# Adafruit_USB_Type_C_PD_Switchable.net
KiCad netlist of a schematic drawn in EAGLE
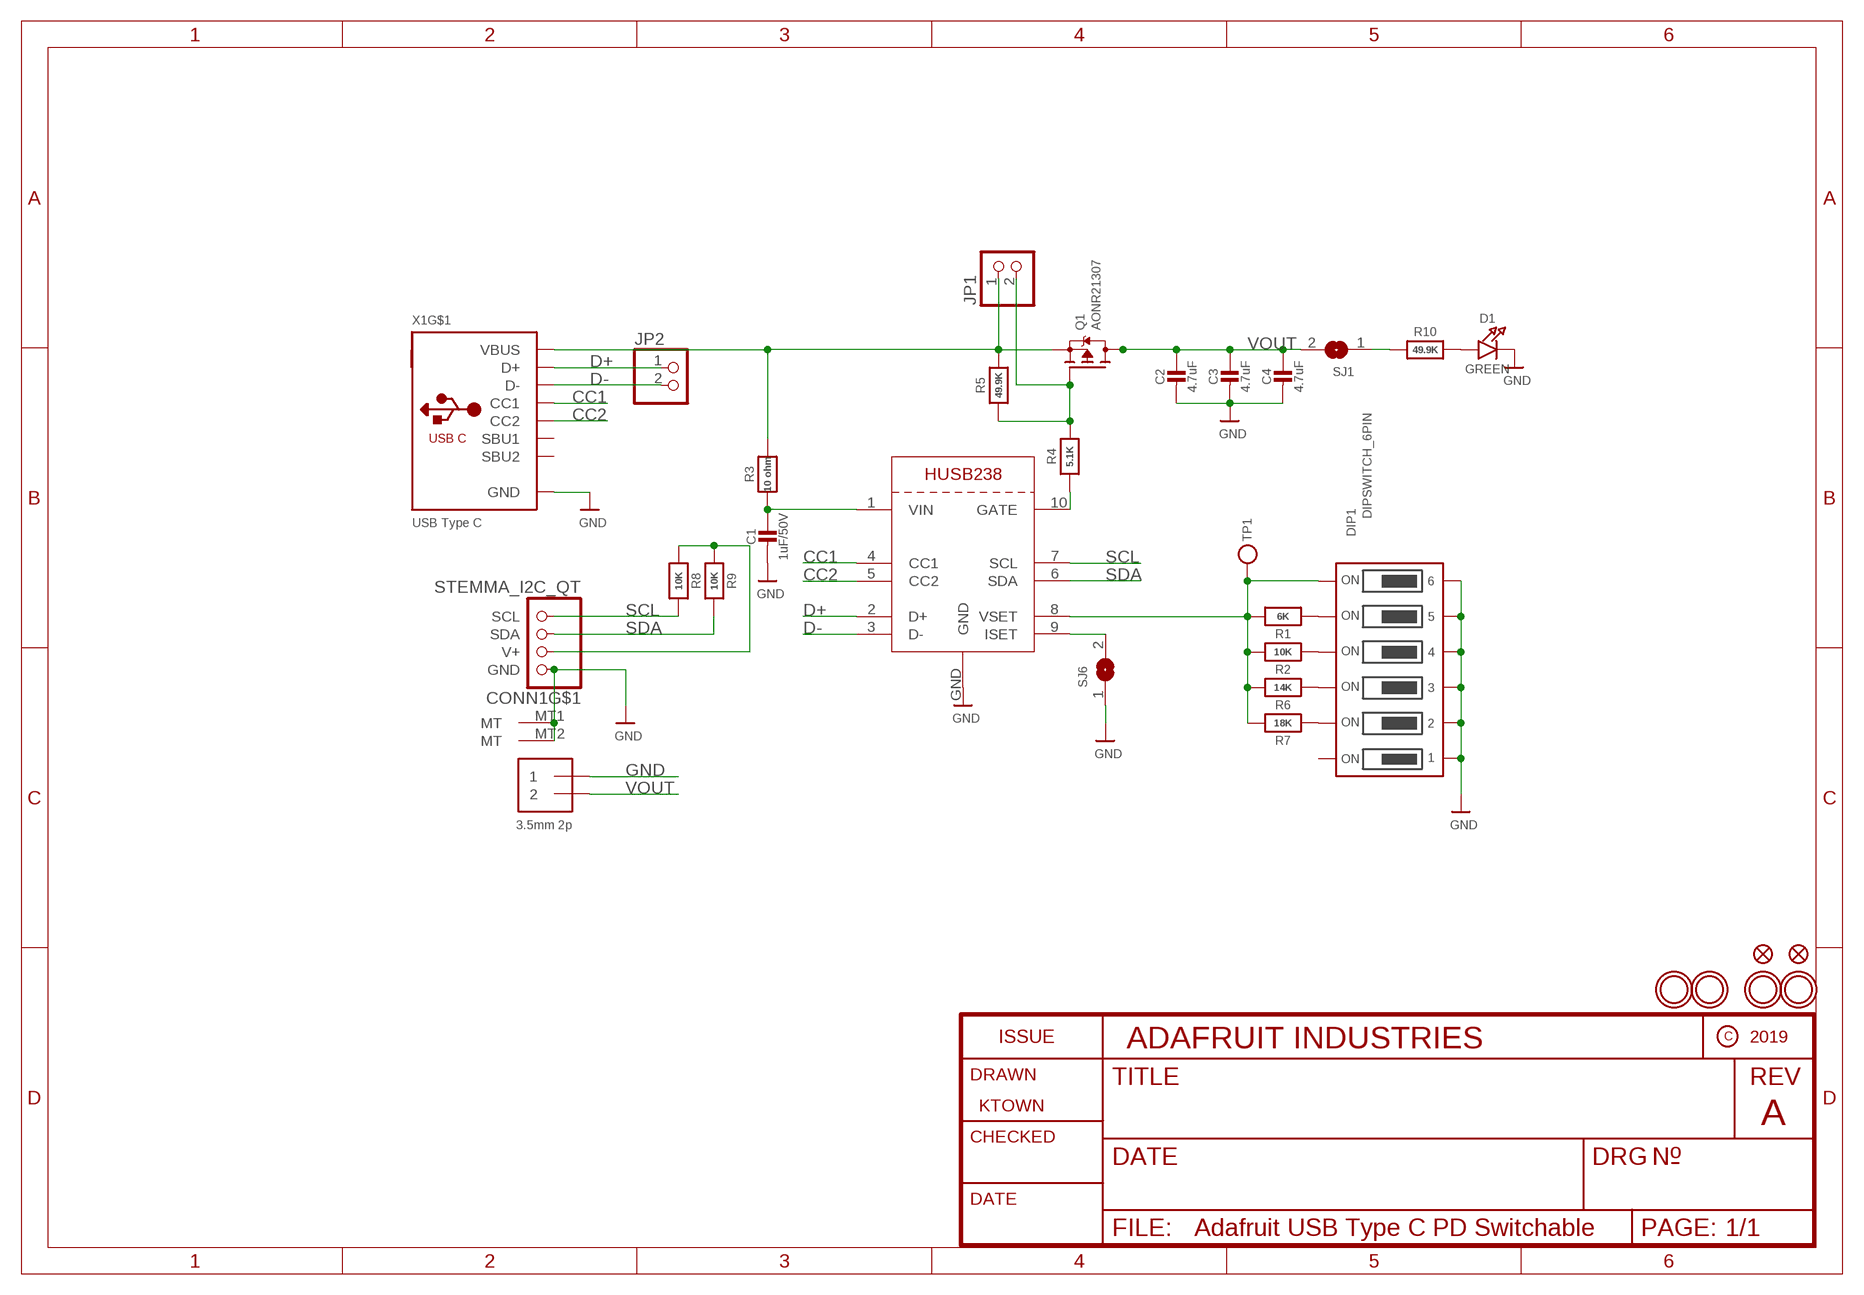
[diagram p0: schematic, sheet 1]

(export (version "E")
  (design (tool "Eeschema 10.0.6"))
  (components
    (comp (ref "C1")
      (value "1uF/50V")
      (footprint "eagle-import:0805-NO")
      (libsource (lib "eagle-import") (part "CAP_CERAMIC0805-NOOUTLINE"))
    )
    (comp (ref "C2")
      (value "4.7uF")
      (footprint "eagle-import:0805-NO")
      (libsource (lib "eagle-import") (part "CAP_CERAMIC0805-NOOUTLINE"))
    )
    (comp (ref "C3")
      (value "4.7uF")
      (footprint "eagle-import:0805-NO")
      (libsource (lib "eagle-import") (part "CAP_CERAMIC0805-NOOUTLINE"))
    )
    (comp (ref "C4")
      (value "4.7uF")
      (footprint "eagle-import:0805-NO")
      (libsource (lib "eagle-import") (part "CAP_CERAMIC0805-NOOUTLINE"))
    )
    (comp (ref "CONN1")
      (value "STEMMA_I2C_QT")
      (footprint "eagle-import:JST_SH4")
      (libsource (lib "eagle-import") (part "STEMMA_I2C_QT"))
    )
    (comp (ref "D1")
      (value "GREEN")
      (footprint "eagle-import:CHIPLED_0603_NOOUTLINE")
      (libsource (lib "eagle-import") (part "LED0603_NOOUTLINE"))
    )
    (comp (ref "DIP1")
      (value "DIPSWITCH_6PIN")
      (footprint "eagle-import:DIPSWITCH_6PIN_1.27")
      (libsource (lib "eagle-import") (part "DIPSWITCH_6PIN"))
    )
    (comp (ref "FID1")
      (value "FIDUCIAL_1MM")
      (footprint "eagle-import:FIDUCIAL_1MM")
      (libsource (lib "eagle-import") (part "FIDUCIAL_1MM"))
    )
    (comp (ref "FID2")
      (value "FIDUCIAL_1MM")
      (footprint "eagle-import:FIDUCIAL_1MM")
      (libsource (lib "eagle-import") (part "FIDUCIAL_1MM"))
    )
    (comp (ref "JP1")
      (value "HEADER-1X2ROUND")
      (footprint "eagle-import:1X02_ROUND")
      (libsource (lib "eagle-import") (part "HEADER-1X2ROUND"))
    )
    (comp (ref "JP2")
      (value "HEADER-1X2ROUND")
      (footprint "eagle-import:1X02_ROUND")
      (libsource (lib "eagle-import") (part "HEADER-1X2ROUND"))
    )
    (comp (ref "Q1")
      (value "AONR21307")
      (footprint "eagle-import:POWERDI3333")
      (libsource (lib "eagle-import") (part "MOSFET-P-POWERDI3333"))
    )
    (comp (ref "R1")
      (value "6K")
      (footprint "eagle-import:_0402NO")
      (libsource (lib "eagle-import") (part "RESISTOR_0402NO"))
    )
    (comp (ref "R2")
      (value "10K")
      (footprint "eagle-import:_0402NO")
      (libsource (lib "eagle-import") (part "RESISTOR_0402NO"))
    )
    (comp (ref "R3")
      (value "10 ohm")
      (footprint "eagle-import:_0402NO")
      (libsource (lib "eagle-import") (part "RESISTOR_0402NO"))
    )
    (comp (ref "R4")
      (value "5.1K")
      (footprint "eagle-import:_0402NO")
      (libsource (lib "eagle-import") (part "RESISTOR_0402NO"))
    )
    (comp (ref "R5")
      (value "49.9K")
      (footprint "eagle-import:_0402NO")
      (libsource (lib "eagle-import") (part "RESISTOR_0402NO"))
    )
    (comp (ref "R6")
      (value "14K")
      (footprint "eagle-import:_0402NO")
      (libsource (lib "eagle-import") (part "RESISTOR_0402NO"))
    )
    (comp (ref "R7")
      (value "18K")
      (footprint "eagle-import:_0402NO")
      (libsource (lib "eagle-import") (part "RESISTOR_0402NO"))
    )
    (comp (ref "R8")
      (value "10K")
      (footprint "eagle-import:_0402NO")
      (libsource (lib "eagle-import") (part "RESISTOR_0402NO"))
    )
    (comp (ref "R9")
      (value "10K")
      (footprint "eagle-import:_0402NO")
      (libsource (lib "eagle-import") (part "RESISTOR_0402NO"))
    )
    (comp (ref "R10")
      (value "49.9K")
      (footprint "eagle-import:_0402NO")
      (libsource (lib "eagle-import") (part "RESISTOR_0402NO"))
    )
    (comp (ref "SJ1")
      (value "SOLDERJUMPERCLOSED")
      (footprint "eagle-import:SOLDERJUMPER_CLOSEDWIRE")
      (libsource (lib "eagle-import") (part "SOLDERJUMPERCLOSED"))
    )
    (comp (ref "SJ6")
      (value "SOLDERJUMPERCLOSED")
      (footprint "eagle-import:SOLDERJUMPER_CLOSEDWIRE")
      (libsource (lib "eagle-import") (part "SOLDERJUMPERCLOSED"))
    )
    (comp (ref "TP1")
      (value "TESTPOINTROUND1.5MMNO")
      (footprint "eagle-import:TESTPOINT_ROUND_1.5MM_NO")
      (libsource (lib "eagle-import") (part "TESTPOINTROUND1.5MMNO"))
    )
    (comp (ref "U$1")
      (value "MOUNTINGHOLE2.5")
      (footprint "eagle-import:MOUNTINGHOLE_2.5_PLATED")
      (libsource (lib "eagle-import") (part "MOUNTINGHOLE2.5"))
    )
    (comp (ref "U$2")
      (value "MOUNTINGHOLE2.5")
      (footprint "eagle-import:MOUNTINGHOLE_2.5_PLATED")
      (libsource (lib "eagle-import") (part "MOUNTINGHOLE2.5"))
    )
    (comp (ref "U$13")
      (value "MOUNTINGHOLE2.5")
      (footprint "eagle-import:MOUNTINGHOLE_2.5_PLATED")
      (libsource (lib "eagle-import") (part "MOUNTINGHOLE2.5"))
    )
    (comp (ref "U$16")
      (value "MOUNTINGHOLE2.5")
      (footprint "eagle-import:MOUNTINGHOLE_2.5_PLATED")
      (libsource (lib "eagle-import") (part "MOUNTINGHOLE2.5"))
    )
    (comp (ref "X1")
      (value "USB Type C")
      (footprint "eagle-import:USB_C_CUSB31-CFM2AX-01-X")
      (libsource (lib "eagle-import") (part "USB_C"))
    )
    (comp (ref "X3")
      (value "HUSB238")
      (footprint "eagle-import:DFN10_3X3MM")
      (libsource (lib "eagle-import") (part "HUSB238"))
    )
    (comp (ref "X4")
      (value "3.5mm 2p")
      (footprint "eagle-import:TERMBLOCK_1X2-3.5MM")
      (fields (field (name "ROT") "0"))
      (libsource (lib "eagle-import") (part "TERMBLOCK_1X2_3.5MM"))
    )
  )
  (nets
    (net (code "1") (name "/CC1") (class "Default")
      (node (ref "X1") (pin "A5") (pinfunction "CC1_A5") (pintype "bidirectional"))
      (node (ref "X3") (pin "4") (pinfunction "CC1_4") (pintype "input"))
    )
    (net (code "2") (name "/CC2") (class "Default")
      (node (ref "X1") (pin "B5") (pinfunction "CC2_B5") (pintype "bidirectional"))
      (node (ref "X3") (pin "5") (pinfunction "CC2_5") (pintype "input"))
    )
    (net (code "3") (name "/D+") (class "Default")
      (node (ref "JP2") (pin "1") (pinfunction "1_1") (pintype "passive"))
      (node (ref "X1") (pin "A6") (pinfunction "D+_A6") (pintype "bidirectional"))
      (node (ref "X1") (pin "B6") (pinfunction "D+_B6") (pintype "bidirectional"))
      (node (ref "X3") (pin "2") (pinfunction "D+_2") (pintype "input"))
    )
    (net (code "4") (name "/D-") (class "Default")
      (node (ref "JP2") (pin "2") (pinfunction "2_2") (pintype "passive"))
      (node (ref "X1") (pin "A7") (pinfunction "D-_A7") (pintype "bidirectional"))
      (node (ref "X1") (pin "B7") (pinfunction "D-_B7") (pintype "bidirectional"))
      (node (ref "X3") (pin "3") (pinfunction "D-_3") (pintype "input"))
    )
    (net (code "5") (name "/SCL") (class "Default")
      (node (ref "CONN1") (pin "4") (pinfunction "SCL_4") (pintype "passive"))
      (node (ref "R8") (pin "2") (pinfunction "2_2") (pintype "passive"))
      (node (ref "X3") (pin "7") (pinfunction "SCL_7") (pintype "bidirectional"))
    )
    (net (code "6") (name "/SDA") (class "Default")
      (node (ref "CONN1") (pin "3") (pinfunction "SDA_3") (pintype "passive"))
      (node (ref "R9") (pin "2") (pinfunction "2_2") (pintype "passive"))
      (node (ref "X3") (pin "6") (pinfunction "SDA_6") (pintype "bidirectional"))
    )
    (net (code "7") (name "/VOUT") (class "Default")
      (node (ref "C2") (pin "1") (pinfunction "1_1") (pintype "passive"))
      (node (ref "C3") (pin "1") (pinfunction "1_1") (pintype "passive"))
      (node (ref "C4") (pin "1") (pinfunction "1_1") (pintype "passive"))
      (node (ref "Q1") (pin "5678") (pinfunction "D_5678") (pintype "passive"))
      (node (ref "SJ1") (pin "2") (pinfunction "2_2") (pintype "passive"))
      (node (ref "X4") (pin "2") (pinfunction "2_2") (pintype "passive"))
    )
    (net (code "8") (name "GND") (class "Default")
      (node (ref "C1") (pin "2") (pinfunction "2_2") (pintype "passive"))
      (node (ref "C2") (pin "2") (pinfunction "2_2") (pintype "passive"))
      (node (ref "C3") (pin "2") (pinfunction "2_2") (pintype "passive"))
      (node (ref "C4") (pin "2") (pinfunction "2_2") (pintype "passive"))
      (node (ref "CONN1") (pin "1") (pinfunction "GND_1") (pintype "passive"))
      (node (ref "CONN1") (pin "MT1") (pinfunction "MT_MT1") (pintype "bidirectional"))
      (node (ref "CONN1") (pin "MT2") (pinfunction "MT_MT2") (pintype "bidirectional"))
      (node (ref "D1") (pin "C") (pinfunction "C_C") (pintype "passive"))
      (node (ref "DIP1") (pin "1OFF") (pinfunction "1OFF_1OFF") (pintype "bidirectional"))
      (node (ref "DIP1") (pin "2OFF") (pinfunction "2OFF_2OFF") (pintype "bidirectional"))
      (node (ref "DIP1") (pin "3OFF") (pinfunction "3OFF_3OFF") (pintype "bidirectional"))
      (node (ref "DIP1") (pin "4OFF") (pinfunction "4OFF_4OFF") (pintype "bidirectional"))
      (node (ref "DIP1") (pin "5OFF") (pinfunction "5OFF_5OFF") (pintype "bidirectional"))
      (node (ref "DIP1") (pin "6OFF") (pinfunction "6OFF_6OFF") (pintype "bidirectional"))
      (node (ref "SJ6") (pin "1") (pinfunction "1_1") (pintype "passive"))
      (node (ref "X1") (pin "A1B12") (pinfunction "GND_A1B12") (pintype "power_in"))
      (node (ref "X1") (pin "B1A12") (pinfunction "GND_B1A12") (pintype "power_in"))
      (node (ref "X3") (pin "GND") (pinfunction "GND_GND") (pintype "power_in"))
      (node (ref "X4") (pin "1") (pinfunction "1_1") (pintype "passive"))
    )
    (net (code "9") (name "Net-(CONN1A-V+)") (class "Default")
      (node (ref "CONN1") (pin "2") (pinfunction "V+_2") (pintype "passive"))
      (node (ref "R8") (pin "1") (pinfunction "1_1") (pintype "passive"))
      (node (ref "R9") (pin "1") (pinfunction "1_1") (pintype "passive"))
    )
    (net (code "10") (name "Net-(D1-PadA)") (class "Default")
      (node (ref "D1") (pin "A") (pinfunction "A_A") (pintype "passive"))
      (node (ref "R10") (pin "2") (pinfunction "2_2") (pintype "passive"))
    )
    (net (code "11") (name "Net-(DIP1-Pad2ON)") (class "Default")
      (node (ref "DIP1") (pin "2ON") (pinfunction "2ON_2ON") (pintype "bidirectional"))
      (node (ref "R7") (pin "1") (pinfunction "1_1") (pintype "passive"))
    )
    (net (code "12") (name "Net-(DIP1-Pad3ON)") (class "Default")
      (node (ref "DIP1") (pin "3ON") (pinfunction "3ON_3ON") (pintype "bidirectional"))
      (node (ref "R6") (pin "1") (pinfunction "1_1") (pintype "passive"))
    )
    (net (code "13") (name "Net-(DIP1-Pad4ON)") (class "Default")
      (node (ref "DIP1") (pin "4ON") (pinfunction "4ON_4ON") (pintype "bidirectional"))
      (node (ref "R2") (pin "1") (pinfunction "1_1") (pintype "passive"))
    )
    (net (code "14") (name "Net-(DIP1-Pad5ON)") (class "Default")
      (node (ref "DIP1") (pin "5ON") (pinfunction "5ON_5ON") (pintype "bidirectional"))
      (node (ref "R1") (pin "1") (pinfunction "1_1") (pintype "passive"))
    )
    (net (code "15") (name "Net-(JP1-Pad1)") (class "Default")
      (node (ref "JP1") (pin "1") (pinfunction "1_1") (pintype "passive"))
      (node (ref "Q1") (pin "1") (pinfunction "S_1") (pintype "passive"))
      (node (ref "Q1") (pin "2") (pinfunction "S_2") (pintype "passive"))
      (node (ref "Q1") (pin "3") (pinfunction "S_3") (pintype "passive"))
      (node (ref "R3") (pin "2") (pinfunction "2_2") (pintype "passive"))
      (node (ref "R5") (pin "1") (pinfunction "1_1") (pintype "passive"))
      (node (ref "X1") (pin "A4B9") (pinfunction "VBUS_A4B9") (pintype "power_in"))
      (node (ref "X1") (pin "B4A9") (pinfunction "VBUS_B4A9") (pintype "power_in"))
    )
    (net (code "16") (name "Net-(Q1-G)") (class "Default")
      (node (ref "JP1") (pin "2") (pinfunction "2_2") (pintype "passive"))
      (node (ref "Q1") (pin "4") (pinfunction "G_4") (pintype "passive"))
      (node (ref "R4") (pin "2") (pinfunction "2_2") (pintype "passive"))
      (node (ref "R5") (pin "2") (pinfunction "2_2") (pintype "passive"))
    )
    (net (code "17") (name "Net-(R10-Pad1)") (class "Default")
      (node (ref "R10") (pin "1") (pinfunction "1_1") (pintype "passive"))
      (node (ref "SJ1") (pin "1") (pinfunction "1_1") (pintype "passive"))
    )
    (net (code "18") (name "Net-(X3-GATE)") (class "Default")
      (node (ref "R4") (pin "1") (pinfunction "1_1") (pintype "passive"))
      (node (ref "X3") (pin "10") (pinfunction "GATE_10") (pintype "output"))
    )
    (net (code "19") (name "Net-(X3-ISET)") (class "Default")
      (node (ref "SJ6") (pin "2") (pinfunction "2_2") (pintype "passive"))
      (node (ref "X3") (pin "9") (pinfunction "ISET_9") (pintype "passive"))
    )
    (net (code "20") (name "Net-(X3-VIN)") (class "Default")
      (node (ref "C1") (pin "1") (pinfunction "1_1") (pintype "passive"))
      (node (ref "R3") (pin "1") (pinfunction "1_1") (pintype "passive"))
      (node (ref "X3") (pin "1") (pinfunction "VIN_1") (pintype "power_in"))
    )
    (net (code "21") (name "Net-(X3-VSET)") (class "Default")
      (node (ref "DIP1") (pin "6ON") (pinfunction "6ON_6ON") (pintype "bidirectional"))
      (node (ref "R1") (pin "2") (pinfunction "2_2") (pintype "passive"))
      (node (ref "R2") (pin "2") (pinfunction "2_2") (pintype "passive"))
      (node (ref "R6") (pin "2") (pinfunction "2_2") (pintype "passive"))
      (node (ref "R7") (pin "2") (pinfunction "2_2") (pintype "passive"))
      (node (ref "TP1") (pin "P$1") (pinfunction "P$1_P$1") (pintype "bidirectional"))
      (node (ref "X3") (pin "8") (pinfunction "VSET_8") (pintype "passive"))
    )
    (net (code "22") (name "unconnected-(DIP1-Pad1ON)") (class "Default")
      (node (ref "DIP1") (pin "1ON") (pinfunction "1ON_1ON") (pintype "bidirectional"))
    )
    (net (code "23") (name "unconnected-(X1A-SBU1-PadA8)") (class "Default")
      (node (ref "X1") (pin "A8") (pinfunction "SBU1_A8") (pintype "bidirectional"))
    )
    (net (code "24") (name "unconnected-(X1A-SBU2-PadB8)") (class "Default")
      (node (ref "X1") (pin "B8") (pinfunction "SBU2_B8") (pintype "bidirectional"))
    )
  )
)
